# Sensor_Borad.net
KiCad netlist of a schematic drawn in Altium Designer
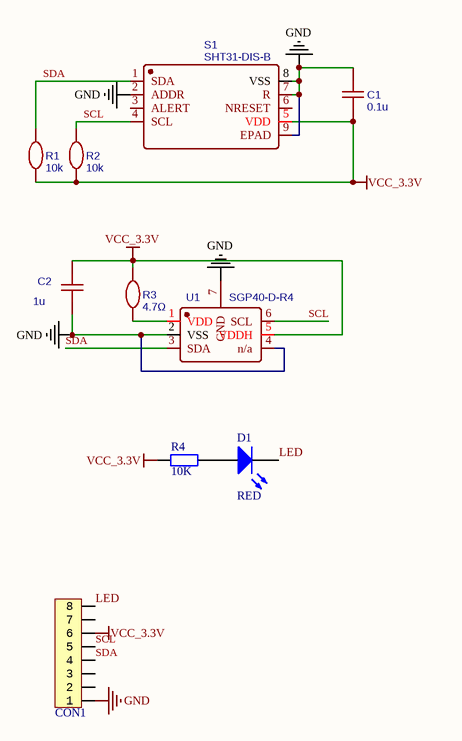
[diagram p0: Sensor_Borad.SchDoc]

(export (version "E")
  (design (tool "Eeschema 10.0.6"))
  (components
    (comp (ref "C1")
      (value "0.1u")
      (footprint "0402_C")
      (fields (field (name "CONTRIBUTOR") "LCEDA_Lib"))
      (libsource (lib "altium-import") (part "root_1_0.1u_"))
    )
    (comp (ref "C2")
      (value "1u")
      (footprint "0402_C")
      (fields (field (name "CONTRIBUTOR") "LCEDA_Lib"))
      (libsource (lib "altium-import") (part "root_1_1u_"))
    )
    (comp (ref "CON1")
      (value "FFC_0.5_8")
      (footprint "FFC_0.5_8")
      (description "FFC")
      (libsource (lib "KitSprout") (part "FFC_0.5_8"))
    )
    (comp (ref "D1")
      (value "RED")
      (footprint "LED_0402_BLUE")
      (description "Typical INFRARED GaAs LED")
      (fields (field (name "PUBLISHER") "Altium Limited"))
      (libsource (lib "Miscellaneous Devices") (part "LED0"))
    )
    (comp (ref "R1")
      (value "10k")
      (footprint "0402_R")
      (fields (field (name "CONTRIBUTOR") "LCEDA_Lib"))
      (libsource (lib "altium-import") (part "root_1_10k_"))
    )
    (comp (ref "R2")
      (value "10k")
      (footprint "0402_R")
      (fields (field (name "CONTRIBUTOR") "LCEDA_Lib"))
      (libsource (lib "altium-import") (part "root_1_10k_"))
    )
    (comp (ref "R3")
      (value "4.7Ω")
      (footprint "0402_R")
      (fields (field (name "CONTRIBUTOR") "LCEDA_Lib"))
      (libsource (lib "altium-import") (part "root_1_4.7Ω_"))
    )
    (comp (ref "R4")
      (value "10K")
      (footprint "0402_R")
      (description "Resistor")
      (fields (field (name "PUBLISHER") "Altium Limited"))
      (libsource (lib "Miscellaneous Devices") (part "Res2"))
    )
    (comp (ref "S1")
      (value "SHT31-DIS-B")
      (footprint "DFN8-P0.50")
      (fields (field (name "BOM_SUPPLIER PART") "C80862"))
      (libsource (lib "altium-import") (part "root_0_SHT31-DIS-B_"))
    )
    (comp (ref "U1")
      (value "SGP40-D-R4")
      (footprint "DFN-6_L2.4-W2.4-P0.80-TL-EP")
      (fields (field (name "BOM_SUPPLIER PART") "C2874215") (field (name "CONTRIBUTOR") "LCSC"))
      (libsource (lib "altium-import") (part "root_0_SGP40-D-R4_"))
    )
  )
  (nets
    (net (code "1") (name "/LED") (class "Default")
      (node (ref "CON1") (pin "8") (pinfunction "8_8") (pintype "passive"))
      (node (ref "D1") (pin "2") (pinfunction "K_2") (pintype "passive"))
    )
    (net (code "2") (name "/SCL") (class "Default")
      (node (ref "CON1") (pin "5") (pinfunction "5_5") (pintype "passive"))
      (node (ref "R2") (pin "2") (pinfunction "2_2") (pintype "passive"))
      (node (ref "S1") (pin "4") (pinfunction "SCL_4") (pintype "passive"))
      (node (ref "U1") (pin "6") (pinfunction "SCL_6") (pintype "passive"))
    )
    (net (code "3") (name "/SDA") (class "Default")
      (node (ref "CON1") (pin "4") (pinfunction "4_4") (pintype "passive"))
      (node (ref "R1") (pin "2") (pinfunction "2_2") (pintype "passive"))
      (node (ref "S1") (pin "1") (pinfunction "SDA_1") (pintype "passive"))
      (node (ref "U1") (pin "3") (pinfunction "SDA_3") (pintype "passive"))
    )
    (net (code "4") (name "GND") (class "Default")
      (node (ref "C1") (pin "2") (pinfunction "2_2") (pintype "passive"))
      (node (ref "C2") (pin "1") (pinfunction "1_1") (pintype "passive"))
      (node (ref "CON1") (pin "1") (pinfunction "1_1") (pintype "passive"))
      (node (ref "S1") (pin "2") (pinfunction "ADDR_2") (pintype "passive"))
      (node (ref "S1") (pin "7") (pinfunction "R_7") (pintype "passive"))
      (node (ref "S1") (pin "8") (pinfunction "VSS_8") (pintype "passive"))
      (node (ref "S1") (pin "9") (pinfunction "EPAD_9") (pintype "passive"))
      (node (ref "U1") (pin "2") (pinfunction "VSS_2") (pintype "passive"))
      (node (ref "U1") (pin "4") (pinfunction "n/a_4") (pintype "passive"))
      (node (ref "U1") (pin "7") (pinfunction "GND_7") (pintype "passive"))
    )
    (net (code "5") (name "Net-(D1-A)") (class "Default")
      (node (ref "D1") (pin "1") (pinfunction "A_1") (pintype "passive"))
      (node (ref "R4") (pin "2") (pinfunction "2_2") (pintype "passive"))
    )
    (net (code "6") (name "Net-(U1-VDD)") (class "Default")
      (node (ref "R3") (pin "1") (pinfunction "1_1") (pintype "passive"))
      (node (ref "U1") (pin "1") (pinfunction "VDD_1") (pintype "passive"))
    )
    (net (code "7") (name "VCC_3.3V") (class "Default")
      (node (ref "C1") (pin "1") (pinfunction "1_1") (pintype "passive"))
      (node (ref "C2") (pin "2") (pinfunction "2_2") (pintype "passive"))
      (node (ref "CON1") (pin "6") (pinfunction "6_6") (pintype "passive"))
      (node (ref "R1") (pin "1") (pinfunction "1_1") (pintype "passive"))
      (node (ref "R2") (pin "1") (pinfunction "1_1") (pintype "passive"))
      (node (ref "R3") (pin "2") (pinfunction "2_2") (pintype "passive"))
      (node (ref "R4") (pin "1") (pinfunction "1_1") (pintype "passive"))
      (node (ref "S1") (pin "5") (pinfunction "VDD_5") (pintype "passive"))
      (node (ref "U1") (pin "5") (pinfunction "VDDH_5") (pintype "passive"))
    )
    (net (code "8") (name "unconnected-(CON1-Pad2)") (class "Default")
      (node (ref "CON1") (pin "2") (pinfunction "2_2") (pintype "passive"))
    )
    (net (code "9") (name "unconnected-(CON1-Pad3)") (class "Default")
      (node (ref "CON1") (pin "3") (pinfunction "3_3") (pintype "passive"))
    )
    (net (code "10") (name "unconnected-(CON1-Pad7)") (class "Default")
      (node (ref "CON1") (pin "7") (pinfunction "7_7") (pintype "passive"))
    )
    (net (code "11") (name "unconnected-(S1-ALERT-Pad3)") (class "Default")
      (node (ref "S1") (pin "3") (pinfunction "ALERT_3") (pintype "passive"))
    )
    (net (code "12") (name "unconnected-(S1-NRESET-Pad6)") (class "Default")
      (node (ref "S1") (pin "6") (pinfunction "NRESET_6") (pintype "passive"))
    )
  )
)
